# MCU.net
KiCad netlist of a schematic drawn in Altium Designer
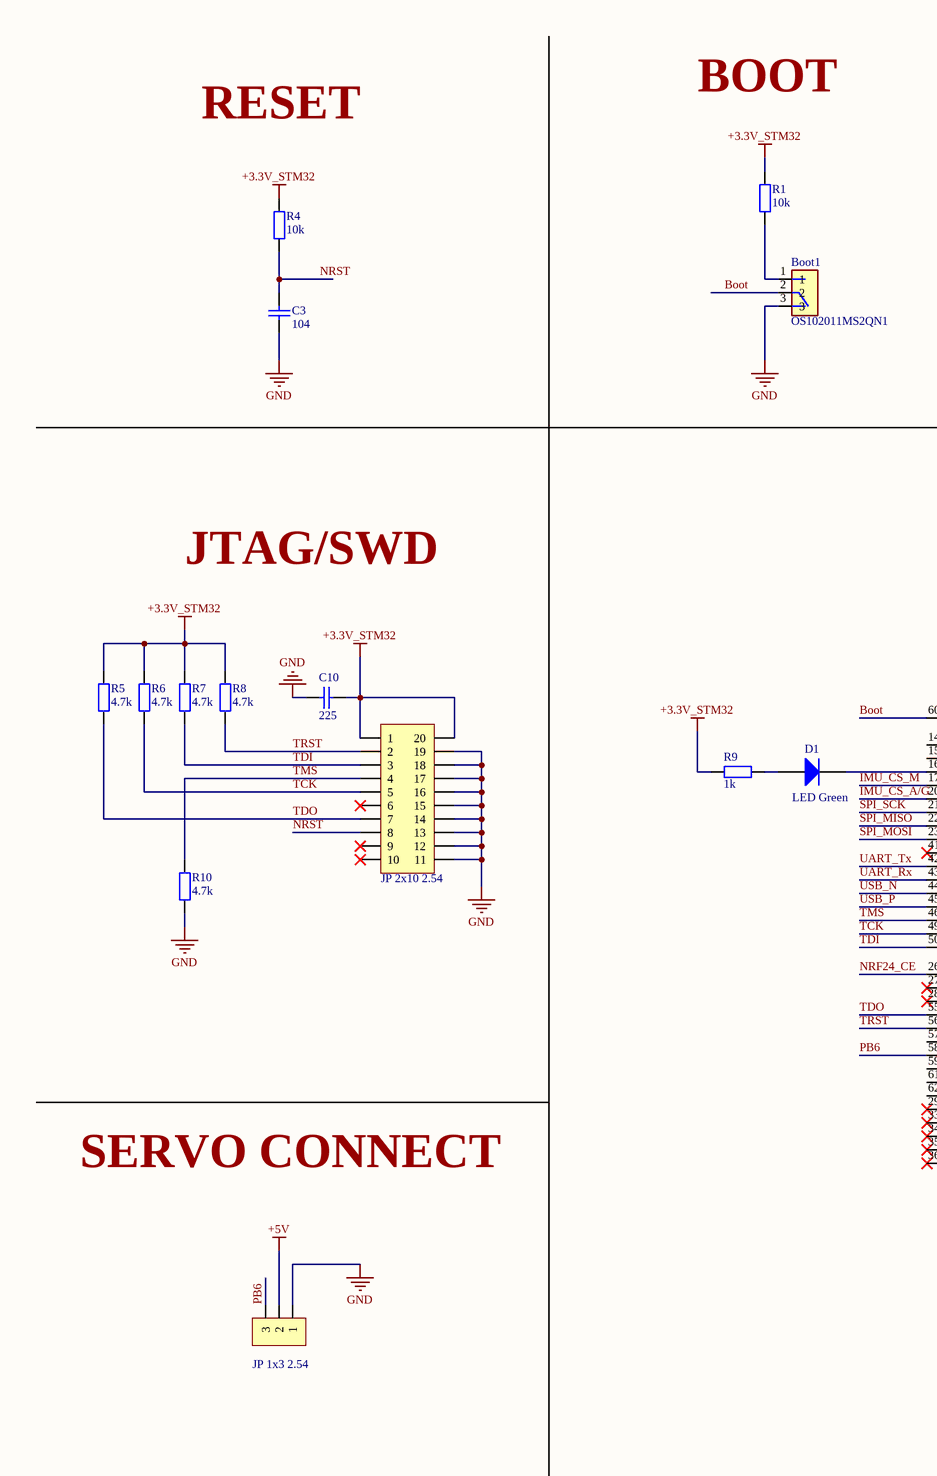
[diagram p0: MCU.SchDoc, left]
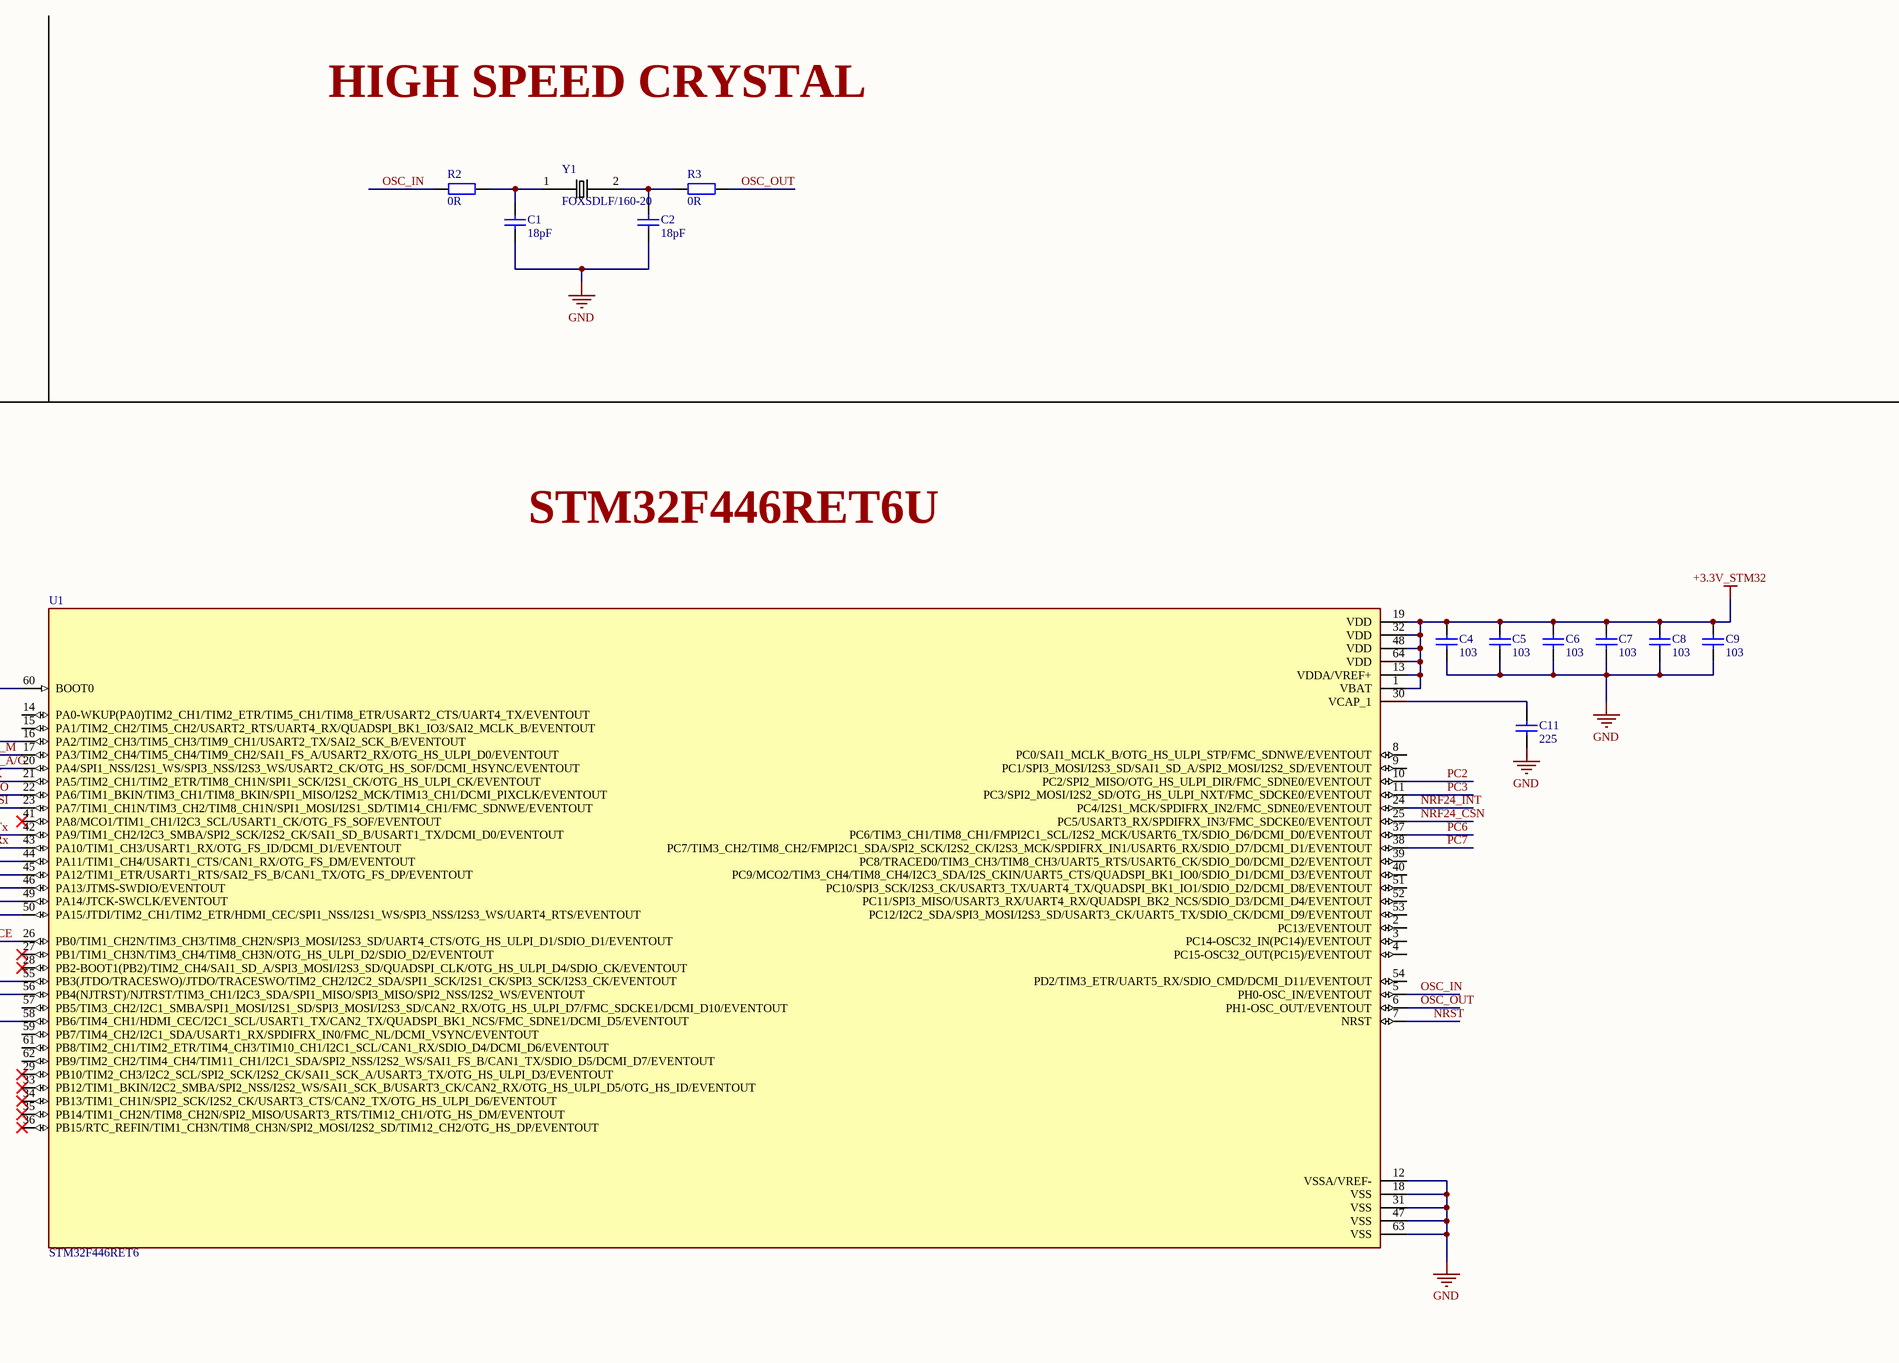
[diagram p1: MCU.SchDoc, right]

(export (version "E")
  (design (tool "Eeschema 10.0.6"))
  (components
    (comp (ref "Boot1")
      (value "OS102011MS2QN1")
      (footprint "OS102011MS2QN1:SW_OS102011MS2QN1")
      (description "Switch Slide ON ON SPDT Top Slide 0.1A 12VDC 10000Cycles PC Pins Thru-Hole Bulk")
      (fields (field (name "MF") "{'manufacturer': u'C&K'}"))
      (libsource (lib "*") (part "OS102011MS2QN1"))
    )
    (comp (ref "C1")
      (value "18pF")
      (footprint "tu 0805")
      (description "Dán")
      (libsource (lib "Altium_Lib_by_KhueNguyenCreator") (part "Tu 0805 20pF 50V 10%"))
    )
    (comp (ref "C2")
      (value "18pF")
      (footprint "tu 0805")
      (description "Dán")
      (libsource (lib "Altium_Lib_by_KhueNguyenCreator") (part "Tu 0805 20pF 50V 10%"))
    )
    (comp (ref "C3")
      (value "104")
      (footprint "tu 1206")
      (description "Dán")
      (libsource (lib "Altium_Lib_by_KhueNguyenCreator") (part "Tu 1206 104 50V 20%"))
    )
    (comp (ref "C4")
      (value "103")
      (footprint "tu 0603")
      (description "Dán")
      (libsource (lib "Altium_Lib_by_KhueNguyenCreator") (part "Tu 0603 103 50V 10%"))
    )
    (comp (ref "C5")
      (value "103")
      (footprint "tu 0603")
      (description "Dán")
      (libsource (lib "Altium_Lib_by_KhueNguyenCreator") (part "Tu 0603 103 50V 10%"))
    )
    (comp (ref "C6")
      (value "103")
      (footprint "tu 0603")
      (description "Dán")
      (libsource (lib "Altium_Lib_by_KhueNguyenCreator") (part "Tu 0603 103 50V 10%"))
    )
    (comp (ref "C7")
      (value "103")
      (footprint "tu 0603")
      (description "Dán")
      (libsource (lib "Altium_Lib_by_KhueNguyenCreator") (part "Tu 0603 103 50V 10%"))
    )
    (comp (ref "C8")
      (value "103")
      (footprint "tu 0603")
      (description "Dán")
      (libsource (lib "Altium_Lib_by_KhueNguyenCreator") (part "Tu 0603 103 50V 10%"))
    )
    (comp (ref "C9")
      (value "103")
      (footprint "tu 0603")
      (description "Dán")
      (libsource (lib "Altium_Lib_by_KhueNguyenCreator") (part "Tu 0603 103 50V 10%"))
    )
    (comp (ref "C10")
      (value "225")
      (footprint "tu 0805")
      (description "Dán")
      (libsource (lib "Altium_Lib_by_KhueNguyenCreator") (part "Tu 0805 225 25V 10%"))
    )
    (comp (ref "C11")
      (value "225")
      (footprint "tu 0805")
      (description "Dán")
      (libsource (lib "Altium_Lib_by_KhueNguyenCreator") (part "Tu 0805 225 25V 10%"))
    )
    (comp (ref "D1")
      (value "LED Green")
      (footprint "J1-0603")
      (description "Default Diode")
      (fields (field (name "PUBLISHER") "Altium Limited"))
      (libsource (lib "MSP430_sch_1060821") (part "Diode"))
    )
    (comp (ref "R1")
      (value "10k")
      (footprint "tro smd 0603")
      (description "Dán")
      (libsource (lib "Altium_Lib_by_KhueNguyenCreator") (part "Tro 0603 1% 10k"))
    )
    (comp (ref "R2")
      (value "0R")
      (footprint "tro smd 0603")
      (description "Dán")
      (libsource (lib "Altium_Lib_by_KhueNguyenCreator") (part "Tro 0603 1% 0R"))
    )
    (comp (ref "R3")
      (value "0R")
      (footprint "tro smd 0603")
      (description "Dán")
      (libsource (lib "Altium_Lib_by_KhueNguyenCreator") (part "Tro 0603 1% 0R"))
    )
    (comp (ref "R4")
      (value "10k")
      (footprint "tro smd 0603")
      (description "Dán")
      (libsource (lib "Altium_Lib_by_KhueNguyenCreator") (part "Tro 0603 1% 10k"))
    )
    (comp (ref "R5")
      (value "4.7k")
      (footprint "tro smd 0603")
      (description "Dán")
      (libsource (lib "Altium_Lib_by_KhueNguyenCreator") (part "Tro 0603 5% 4.7k"))
    )
    (comp (ref "R6")
      (value "4.7k")
      (footprint "tro smd 0603")
      (description "Dán")
      (libsource (lib "Altium_Lib_by_KhueNguyenCreator") (part "Tro 0603 5% 4.7k"))
    )
    (comp (ref "R7")
      (value "4.7k")
      (footprint "tro smd 0603")
      (description "Dán")
      (libsource (lib "Altium_Lib_by_KhueNguyenCreator") (part "Tro 0603 5% 4.7k"))
    )
    (comp (ref "R8")
      (value "4.7k")
      (footprint "tro smd 0603")
      (description "Dán")
      (libsource (lib "Altium_Lib_by_KhueNguyenCreator") (part "Tro 0603 5% 4.7k"))
    )
    (comp (ref "R9")
      (value "1k")
      (footprint "tro smd 0603")
      (description "Dán")
      (libsource (lib "Altium_Lib_by_KhueNguyenCreator") (part "Tro 0603 1% 1k"))
    )
    (comp (ref "R10")
      (value "4.7k")
      (footprint "tro smd 0603")
      (description "Dán")
      (libsource (lib "Altium_Lib_by_KhueNguyenCreator") (part "Tro 0603 5% 4.7k"))
    )
    (comp (ref "Servo1")
      (value "JP 1x3 2.54")
      (footprint "JP 1x3 DT")
      (description "Cắm")
      (libsource (lib "Altium_Lib_by_KhueNguyenCreator") (part "JP 1x3 2.54 Duc Thang"))
    )
    (comp (ref "SWD/JTAG1")
      (value "JP 2x10 2.54")
      (footprint "JP 2x10 DT")
      (description "Cắm")
      (libsource (lib "Altium_Lib_by_KhueNguyenCreator") (part "JP 2x10 2.54 Duc Thang"))
    )
    (comp (ref "U1")
      (value "STM32F446RET6")
      (footprint "STM32F446RET6:QFP50P1200X1200X160-64N")
      (description "MCU 32-Bit STM32 ARM Cortex M4 RISC 512KB Flash 2.5V/3.3V 64-Pin LQFP Tray")
      (fields (field (name "MF") "{'manufacturer': u'STMicroelectronics'}"))
      (libsource (lib "*") (part "STM32F446RET6"))
    )
    (comp (ref "Y1")
      (value "FOXSDLF/160-20")
      (footprint "SMD_Crystal")
      (description "Crystal 16MHz 20pF 2-Pin HC-49/SD")
      (fields (field (name "DIGI-KEY_PART_NUMBER") "631-1017-2-ND") (field (name "MF") "Fox"))
      (libsource (lib "MSP430_sch_1120816") (part "Crystal 16MHz 20pF 2-Pin"))
    )
  )
  (nets
    (net (code "1") (name "+3.3V_STM32") (class "Default")
      (node (ref "C10") (pin "1") (pinfunction "1_1") (pintype "passive"))
      (node (ref "C4") (pin "1") (pinfunction "1_1") (pintype "passive"))
      (node (ref "C5") (pin "1") (pinfunction "1_1") (pintype "passive"))
      (node (ref "C6") (pin "1") (pinfunction "1_1") (pintype "passive"))
      (node (ref "C7") (pin "1") (pinfunction "1_1") (pintype "passive"))
      (node (ref "C8") (pin "1") (pinfunction "1_1") (pintype "passive"))
      (node (ref "C9") (pin "1") (pinfunction "1_1") (pintype "passive"))
      (node (ref "R1") (pin "2") (pinfunction "2_2") (pintype "passive"))
      (node (ref "R4") (pin "2") (pinfunction "2_2") (pintype "passive"))
      (node (ref "R5") (pin "2") (pinfunction "2_2") (pintype "passive"))
      (node (ref "R6") (pin "2") (pinfunction "2_2") (pintype "passive"))
      (node (ref "R7") (pin "2") (pinfunction "2_2") (pintype "passive"))
      (node (ref "R8") (pin "2") (pinfunction "2_2") (pintype "passive"))
      (node (ref "R9") (pin "2") (pinfunction "2_2") (pintype "passive"))
      (node (ref "SWD/JTAG1") (pin "1") (pinfunction "1_1") (pintype "passive"))
      (node (ref "SWD/JTAG1") (pin "20") (pinfunction "20_20") (pintype "passive"))
      (node (ref "U1") (pin "1") (pinfunction "VBAT_1") (pintype "power_in"))
      (node (ref "U1") (pin "13") (pinfunction "VDDA/VREF+_13") (pintype "power_in"))
      (node (ref "U1") (pin "19") (pinfunction "VDD_19") (pintype "power_in"))
      (node (ref "U1") (pin "32") (pinfunction "VDD_32") (pintype "power_in"))
      (node (ref "U1") (pin "48") (pinfunction "VDD_48") (pintype "power_in"))
      (node (ref "U1") (pin "64") (pinfunction "VDD_64") (pintype "power_in"))
    )
    (net (code "2") (name "+5V") (class "Default")
      (node (ref "Servo1") (pin "2") (pinfunction "2_2") (pintype "passive"))
    )
    (net (code "3") (name "/Boot") (class "Default")
      (node (ref "Boot1") (pin "2") (pinfunction "2_2") (pintype "passive"))
      (node (ref "U1") (pin "60") (pinfunction "BOOT0_60") (pintype "input"))
    )
    (net (code "4") (name "/IMU_CS_A{slash}G") (class "Default")
      (node (ref "U1") (pin "20") (pinfunction "PA4/SPI1_NSS/I2S1_WS/SPI3_NSS/I2S3_WS/USART2_CK/OTG_HS_SOF/DCMI_HSYNC/EVENTOUT_20") (pintype "bidirectional"))
    )
    (net (code "5") (name "/IMU_CS_M") (class "Default")
      (node (ref "U1") (pin "17") (pinfunction "PA3/TIM2_CH4/TIM5_CH4/TIM9_CH2/SAI1_FS_A/USART2_RX/OTG_HS_ULPI_D0/EVENTOUT_17") (pintype "bidirectional"))
    )
    (net (code "6") (name "/NRF24_CE") (class "Default")
      (node (ref "U1") (pin "26") (pinfunction "PB0/TIM1_CH2N/TIM3_CH3/TIM8_CH2N/SPI3_MOSI/I2S3_SD/UART4_CTS/OTG_HS_ULPI_D1/SDIO_D1/EVENTOUT_26") (pintype "bidirectional"))
    )
    (net (code "7") (name "/NRF24_CSN") (class "Default")
      (node (ref "U1") (pin "25") (pinfunction "PC5/USART3_RX/SPDIFRX_IN3/FMC_SDCKE0/EVENTOUT_25") (pintype "bidirectional"))
    )
    (net (code "8") (name "/NRF24_INT") (class "Default")
      (node (ref "U1") (pin "24") (pinfunction "PC4/I2S1_MCK/SPDIFRX_IN2/FMC_SDNE0/EVENTOUT_24") (pintype "bidirectional"))
    )
    (net (code "9") (name "/NRST") (class "Default")
      (node (ref "C3") (pin "1") (pinfunction "1_1") (pintype "passive"))
      (node (ref "R4") (pin "1") (pinfunction "1_1") (pintype "passive"))
      (node (ref "SWD/JTAG1") (pin "8") (pinfunction "8_8") (pintype "passive"))
      (node (ref "U1") (pin "7") (pinfunction "NRST_7") (pintype "bidirectional"))
    )
    (net (code "10") (name "/OSC_IN") (class "Default")
      (node (ref "R2") (pin "1") (pinfunction "1_1") (pintype "passive"))
      (node (ref "U1") (pin "5") (pinfunction "PH0-OSC_IN/EVENTOUT_5") (pintype "bidirectional"))
    )
    (net (code "11") (name "/OSC_OUT") (class "Default")
      (node (ref "R3") (pin "2") (pinfunction "2_2") (pintype "passive"))
      (node (ref "U1") (pin "6") (pinfunction "PH1-OSC_OUT/EVENTOUT_6") (pintype "bidirectional"))
    )
    (net (code "12") (name "/PB6") (class "Default")
      (node (ref "Servo1") (pin "3") (pinfunction "3_3") (pintype "passive"))
      (node (ref "U1") (pin "58") (pinfunction "PB6/TIM4_CH1/HDMI_CEC/I2C1_SCL/USART1_TX/CAN2_TX/QUADSPI_BK1_NCS/FMC_SDNE1/DCMI_D5/EVENTOUT_58") (pintype "bidirectional"))
    )
    (net (code "13") (name "/PC2") (class "Default")
      (node (ref "U1") (pin "10") (pinfunction "PC2/SPI2_MISO/OTG_HS_ULPI_DIR/FMC_SDNE0/EVENTOUT_10") (pintype "bidirectional"))
    )
    (net (code "14") (name "/PC3") (class "Default")
      (node (ref "U1") (pin "11") (pinfunction "PC3/SPI2_MOSI/I2S2_SD/OTG_HS_ULPI_NXT/FMC_SDCKE0/EVENTOUT_11") (pintype "bidirectional"))
    )
    (net (code "15") (name "/PC6") (class "Default")
      (node (ref "U1") (pin "37") (pinfunction "PC6/TIM3_CH1/TIM8_CH1/FMPI2C1_SCL/I2S2_MCK/USART6_TX/SDIO_D6/DCMI_D0/EVENTOUT_37") (pintype "bidirectional"))
    )
    (net (code "16") (name "/PC7") (class "Default")
      (node (ref "U1") (pin "38") (pinfunction "PC7/TIM3_CH2/TIM8_CH2/FMPI2C1_SDA/SPI2_SCK/I2S2_CK/I2S3_MCK/SPDIFRX_IN1/USART6_RX/SDIO_D7/DCMI_D1/EVENTOUT_38") (pintype "bidirectional"))
    )
    (net (code "17") (name "/SPI_MISO") (class "Default")
      (node (ref "U1") (pin "22") (pinfunction "PA6/TIM1_BKIN/TIM3_CH1/TIM8_BKIN/SPI1_MISO/I2S2_MCK/TIM13_CH1/DCMI_PIXCLK/EVENTOUT_22") (pintype "bidirectional"))
    )
    (net (code "18") (name "/SPI_MOSI") (class "Default")
      (node (ref "U1") (pin "23") (pinfunction "PA7/TIM1_CH1N/TIM3_CH2/TIM8_CH1N/SPI1_MOSI/I2S1_SD/TIM14_CH1/FMC_SDNWE/EVENTOUT_23") (pintype "bidirectional"))
    )
    (net (code "19") (name "/SPI_SCK") (class "Default")
      (node (ref "U1") (pin "21") (pinfunction "PA5/TIM2_CH1/TIM2_ETR/TIM8_CH1N/SPI1_SCK/I2S1_CK/OTG_HS_ULPI_CK/EVENTOUT_21") (pintype "bidirectional"))
    )
    (net (code "20") (name "/TCK") (class "Default")
      (node (ref "R6") (pin "1") (pinfunction "1_1") (pintype "passive"))
      (node (ref "SWD/JTAG1") (pin "5") (pinfunction "5_5") (pintype "passive"))
      (node (ref "U1") (pin "49") (pinfunction "PA14/JTCK-SWCLK/EVENTOUT_49") (pintype "bidirectional"))
    )
    (net (code "21") (name "/TDI") (class "Default")
      (node (ref "R7") (pin "1") (pinfunction "1_1") (pintype "passive"))
      (node (ref "SWD/JTAG1") (pin "3") (pinfunction "3_3") (pintype "passive"))
      (node (ref "U1") (pin "50") (pinfunction "PA15/JTDI/TIM2_CH1/TIM2_ETR/HDMI_CEC/SPI1_NSS/I2S1_WS/SPI3_NSS/I2S3_WS/UART4_RTS/EVENTOUT_50") (pintype "bidirectional"))
    )
    (net (code "22") (name "/TDO") (class "Default")
      (node (ref "R5") (pin "1") (pinfunction "1_1") (pintype "passive"))
      (node (ref "SWD/JTAG1") (pin "7") (pinfunction "7_7") (pintype "passive"))
      (node (ref "U1") (pin "55") (pinfunction "PB3(JTDO/TRACESWO)/JTDO/TRACESWO/TIM2_CH2/I2C2_SDA/SPI1_SCK/I2S1_CK/SPI3_SCK/I2S3_CK/EVENTOUT_55") (pintype "bidirectional"))
    )
    (net (code "23") (name "/TMS") (class "Default")
      (node (ref "R10") (pin "2") (pinfunction "2_2") (pintype "passive"))
      (node (ref "SWD/JTAG1") (pin "4") (pinfunction "4_4") (pintype "passive"))
      (node (ref "U1") (pin "46") (pinfunction "PA13/JTMS-SWDIO/EVENTOUT_46") (pintype "bidirectional"))
    )
    (net (code "24") (name "/TRST") (class "Default")
      (node (ref "R8") (pin "1") (pinfunction "1_1") (pintype "passive"))
      (node (ref "SWD/JTAG1") (pin "2") (pinfunction "2_2") (pintype "passive"))
      (node (ref "U1") (pin "56") (pinfunction "PB4(NJTRST)/NJTRST/TIM3_CH1/I2C3_SDA/SPI1_MISO/SPI3_MISO/SPI2_NSS/I2S2_WS/EVENTOUT_56") (pintype "bidirectional"))
    )
    (net (code "25") (name "/UART_Rx") (class "Default")
      (node (ref "U1") (pin "43") (pinfunction "PA10/TIM1_CH3/USART1_RX/OTG_FS_ID/DCMI_D1/EVENTOUT_43") (pintype "bidirectional"))
    )
    (net (code "26") (name "/UART_Tx") (class "Default")
      (node (ref "U1") (pin "42") (pinfunction "PA9/TIM1_CH2/I2C3_SMBA/SPI2_SCK/I2S2_CK/SAI1_SD_B/USART1_TX/DCMI_D0/EVENTOUT_42") (pintype "bidirectional"))
    )
    (net (code "27") (name "/USB_N") (class "Default")
      (node (ref "U1") (pin "44") (pinfunction "PA11/TIM1_CH4/USART1_CTS/CAN1_RX/OTG_FS_DM/EVENTOUT_44") (pintype "bidirectional"))
    )
    (net (code "28") (name "/USB_P") (class "Default")
      (node (ref "U1") (pin "45") (pinfunction "PA12/TIM1_ETR/USART1_RTS/SAI2_FS_B/CAN1_TX/OTG_FS_DP/EVENTOUT_45") (pintype "bidirectional"))
    )
    (net (code "29") (name "GND") (class "Default")
      (node (ref "Boot1") (pin "3") (pinfunction "3_3") (pintype "passive"))
      (node (ref "C1") (pin "2") (pinfunction "2_2") (pintype "passive"))
      (node (ref "C10") (pin "2") (pinfunction "2_2") (pintype "passive"))
      (node (ref "C11") (pin "2") (pinfunction "2_2") (pintype "passive"))
      (node (ref "C2") (pin "2") (pinfunction "2_2") (pintype "passive"))
      (node (ref "C3") (pin "2") (pinfunction "2_2") (pintype "passive"))
      (node (ref "C4") (pin "2") (pinfunction "2_2") (pintype "passive"))
      (node (ref "C5") (pin "2") (pinfunction "2_2") (pintype "passive"))
      (node (ref "C6") (pin "2") (pinfunction "2_2") (pintype "passive"))
      (node (ref "C7") (pin "2") (pinfunction "2_2") (pintype "passive"))
      (node (ref "C8") (pin "2") (pinfunction "2_2") (pintype "passive"))
      (node (ref "C9") (pin "2") (pinfunction "2_2") (pintype "passive"))
      (node (ref "R10") (pin "1") (pinfunction "1_1") (pintype "passive"))
      (node (ref "SWD/JTAG1") (pin "11") (pinfunction "11_11") (pintype "passive"))
      (node (ref "SWD/JTAG1") (pin "12") (pinfunction "12_12") (pintype "passive"))
      (node (ref "SWD/JTAG1") (pin "13") (pinfunction "13_13") (pintype "passive"))
      (node (ref "SWD/JTAG1") (pin "14") (pinfunction "14_14") (pintype "passive"))
      (node (ref "SWD/JTAG1") (pin "15") (pinfunction "15_15") (pintype "passive"))
      (node (ref "SWD/JTAG1") (pin "16") (pinfunction "16_16") (pintype "passive"))
      (node (ref "SWD/JTAG1") (pin "17") (pinfunction "17_17") (pintype "passive"))
      (node (ref "SWD/JTAG1") (pin "18") (pinfunction "18_18") (pintype "passive"))
      (node (ref "SWD/JTAG1") (pin "19") (pinfunction "19_19") (pintype "passive"))
      (node (ref "Servo1") (pin "1") (pinfunction "1_1") (pintype "passive"))
      (node (ref "U1") (pin "12") (pinfunction "VSSA/VREF-_12") (pintype "power_in"))
      (node (ref "U1") (pin "18") (pinfunction "VSS_18") (pintype "power_in"))
      (node (ref "U1") (pin "31") (pinfunction "VSS_31") (pintype "power_in"))
      (node (ref "U1") (pin "47") (pinfunction "VSS_47") (pintype "power_in"))
      (node (ref "U1") (pin "63") (pinfunction "VSS_63") (pintype "power_in"))
    )
    (net (code "30") (name "Net-(Boot1-Pad1)") (class "Default")
      (node (ref "Boot1") (pin "1") (pinfunction "1_1") (pintype "passive"))
      (node (ref "R1") (pin "1") (pinfunction "1_1") (pintype "passive"))
    )
    (net (code "31") (name "Net-(C1-Pad1)") (class "Default")
      (node (ref "C1") (pin "1") (pinfunction "1_1") (pintype "passive"))
      (node (ref "R2") (pin "2") (pinfunction "2_2") (pintype "passive"))
      (node (ref "Y1") (pin "1") (pinfunction "1_1") (pintype "passive"))
    )
    (net (code "32") (name "Net-(C2-Pad1)") (class "Default")
      (node (ref "C2") (pin "1") (pinfunction "1_1") (pintype "passive"))
      (node (ref "R3") (pin "1") (pinfunction "1_1") (pintype "passive"))
      (node (ref "Y1") (pin "2") (pinfunction "2_2") (pintype "passive"))
    )
    (net (code "33") (name "Net-(D1-A)") (class "Default")
      (node (ref "D1") (pin "1") (pinfunction "A_1") (pintype "passive"))
      (node (ref "R9") (pin "1") (pinfunction "1_1") (pintype "passive"))
    )
    (net (code "34") (name "Net-(D1-K)") (class "Default")
      (node (ref "D1") (pin "2") (pinfunction "K_2") (pintype "passive"))
      (node (ref "U1") (pin "16") (pinfunction "PA2/TIM2_CH3/TIM5_CH3/TIM9_CH1/USART2_TX/SAI2_SCK_B/EVENTOUT_16") (pintype "bidirectional"))
    )
    (net (code "35") (name "Net-(U1-VCAP_1)") (class "Default")
      (node (ref "C11") (pin "1") (pinfunction "1_1") (pintype "passive"))
      (node (ref "U1") (pin "30") (pinfunction "VCAP_1_30") (pintype "power_in"))
    )
    (net (code "36") (name "unconnected-(SWD/JTAG1-Pad6)") (class "Default")
      (node (ref "SWD/JTAG1") (pin "6") (pinfunction "6_6") (pintype "passive+no_connect"))
    )
    (net (code "37") (name "unconnected-(SWD/JTAG1-Pad9)") (class "Default")
      (node (ref "SWD/JTAG1") (pin "9") (pinfunction "9_9") (pintype "passive+no_connect"))
    )
    (net (code "38") (name "unconnected-(SWD/JTAG1-Pad10)") (class "Default")
      (node (ref "SWD/JTAG1") (pin "10") (pinfunction "10_10") (pintype "passive+no_connect"))
    )
    (net (code "39") (name "unconnected-(U1-PA0-WKUP(PA0)TIM2_CH1{slash}TIM2_ETR{slash}TIM5_CH1{slash}TIM8_ETR{slash}USART2_CTS{slash}UART4_TX{slash}EVENTOUT-Pad14)") (class "Default")
      (node (ref "U1") (pin "14") (pinfunction "PA0-WKUP(PA0)TIM2_CH1/TIM2_ETR/TIM5_CH1/TIM8_ETR/USART2_CTS/UART4_TX/EVENTOUT_14") (pintype "bidirectional"))
    )
    (net (code "40") (name "unconnected-(U1-PA1{slash}TIM2_CH2{slash}TIM5_CH2{slash}USART2_RTS{slash}UART4_RX{slash}QUADSPI_BK1_IO3{slash}SAI2_MCLK_B{slash}EVENTOUT-Pad15)") (class "Default")
      (node (ref "U1") (pin "15") (pinfunction "PA1/TIM2_CH2/TIM5_CH2/USART2_RTS/UART4_RX/QUADSPI_BK1_IO3/SAI2_MCLK_B/EVENTOUT_15") (pintype "bidirectional"))
    )
    (net (code "41") (name "unconnected-(U1-PA8{slash}MCO1{slash}TIM1_CH1{slash}I2C3_SCL{slash}USART1_CK{slash}OTG_FS_SOF{slash}EVENTOUT-Pad41)") (class "Default")
      (node (ref "U1") (pin "41") (pinfunction "PA8/MCO1/TIM1_CH1/I2C3_SCL/USART1_CK/OTG_FS_SOF/EVENTOUT_41") (pintype "bidirectional+no_connect"))
    )
    (net (code "42") (name "unconnected-(U1-PB1{slash}TIM1_CH3N{slash}TIM3_CH4{slash}TIM8_CH3N{slash}OTG_HS_ULPI_D2{slash}SDIO_D2{slash}EVENTOUT-Pad27)") (class "Default")
      (node (ref "U1") (pin "27") (pinfunction "PB1/TIM1_CH3N/TIM3_CH4/TIM8_CH3N/OTG_HS_ULPI_D2/SDIO_D2/EVENTOUT_27") (pintype "bidirectional+no_connect"))
    )
    (net (code "43") (name "unconnected-(U1-PB2-BOOT1(PB2){slash}TIM2_CH4{slash}SAI1_SD_A{slash}SPI3_MOSI{slash}I2S3_SD{slash}QUADSPI_CLK{slash}OTG_HS_ULPI_D4{slash}SDIO_CK{slash}EVENTOUT-Pad28)") (class "Default")
      (node (ref "U1") (pin "28") (pinfunction "PB2-BOOT1(PB2)/TIM2_CH4/SAI1_SD_A/SPI3_MOSI/I2S3_SD/QUADSPI_CLK/OTG_HS_ULPI_D4/SDIO_CK/EVENTOUT_28") (pintype "bidirectional+no_connect"))
    )
    (net (code "44") (name "unconnected-(U1-PB5{slash}TIM3_CH2{slash}I2C1_SMBA{slash}SPI1_MOSI{slash}I2S1_SD{slash}SPI3_MOSI{slash}I2S3_SD{slash}CAN2_RX{slash}OTG_HS_ULPI_D7{slash}FMC_SDCKE1{slash}DCMI_D10{slash}EVENTOUT-Pad57)") (class "Default")
      (node (ref "U1") (pin "57") (pinfunction "PB5/TIM3_CH2/I2C1_SMBA/SPI1_MOSI/I2S1_SD/SPI3_MOSI/I2S3_SD/CAN2_RX/OTG_HS_ULPI_D7/FMC_SDCKE1/DCMI_D10/EVENTOUT_57") (pintype "bidirectional"))
    )
    (net (code "45") (name "unconnected-(U1-PB7{slash}TIM4_CH2{slash}I2C1_SDA{slash}USART1_RX{slash}SPDIFRX_IN0{slash}FMC_NL{slash}DCMI_VSYNC{slash}EVENTOUT-Pad59)") (class "Default")
      (node (ref "U1") (pin "59") (pinfunction "PB7/TIM4_CH2/I2C1_SDA/USART1_RX/SPDIFRX_IN0/FMC_NL/DCMI_VSYNC/EVENTOUT_59") (pintype "bidirectional"))
    )
    (net (code "46") (name "unconnected-(U1-PB8{slash}TIM2_CH1{slash}TIM2_ETR{slash}TIM4_CH3{slash}TIM10_CH1{slash}I2C1_SCL{slash}CAN1_RX{slash}SDIO_D4{slash}DCMI_D6{slash}EVENTOUT-Pad61)") (class "Default")
      (node (ref "U1") (pin "61") (pinfunction "PB8/TIM2_CH1/TIM2_ETR/TIM4_CH3/TIM10_CH1/I2C1_SCL/CAN1_RX/SDIO_D4/DCMI_D6/EVENTOUT_61") (pintype "bidirectional"))
    )
    (net (code "47") (name "unconnected-(U1-PB9{slash}TIM2_CH2{slash}TIM4_CH4{slash}TIM11_CH1{slash}I2C1_SDA{slash}SPI2_NSS{slash}I2S2_WS{slash}SAI1_FS_B{slash}CAN1_TX{slash}SDIO_D5{slash}DCMI_D7{slash}EVENTOUT-Pad62)") (class "Default")
      (node (ref "U1") (pin "62") (pinfunction "PB9/TIM2_CH2/TIM4_CH4/TIM11_CH1/I2C1_SDA/SPI2_NSS/I2S2_WS/SAI1_FS_B/CAN1_TX/SDIO_D5/DCMI_D7/EVENTOUT_62") (pintype "bidirectional"))
    )
    (net (code "48") (name "unconnected-(U1-PB10{slash}TIM2_CH3{slash}I2C2_SCL{slash}SPI2_SCK{slash}I2S2_CK{slash}SAI1_SCK_A{slash}USART3_TX{slash}OTG_HS_ULPI_D3{slash}EVENTOUT-Pad29)") (class "Default")
      (node (ref "U1") (pin "29") (pinfunction "PB10/TIM2_CH3/I2C2_SCL/SPI2_SCK/I2S2_CK/SAI1_SCK_A/USART3_TX/OTG_HS_ULPI_D3/EVENTOUT_29") (pintype "bidirectional+no_connect"))
    )
    (net (code "49") (name "unconnected-(U1-PB12{slash}TIM1_BKIN{slash}I2C2_SMBA{slash}SPI2_NSS{slash}I2S2_WS{slash}SAI1_SCK_B{slash}USART3_CK{slash}CAN2_RX{slash}OTG_HS_ULPI_D5{slash}OTG_HS_ID{slash}EVENTOUT-Pad33)") (class "Default")
      (node (ref "U1") (pin "33") (pinfunction "PB12/TIM1_BKIN/I2C2_SMBA/SPI2_NSS/I2S2_WS/SAI1_SCK_B/USART3_CK/CAN2_RX/OTG_HS_ULPI_D5/OTG_HS_ID/EVENTOUT_33") (pintype "bidirectional+no_connect"))
    )
    (net (code "50") (name "unconnected-(U1-PB13{slash}TIM1_CH1N{slash}SPI2_SCK{slash}I2S2_CK{slash}USART3_CTS{slash}CAN2_TX{slash}OTG_HS_ULPI_D6{slash}EVENTOUT-Pad34)") (class "Default")
      (node (ref "U1") (pin "34") (pinfunction "PB13/TIM1_CH1N/SPI2_SCK/I2S2_CK/USART3_CTS/CAN2_TX/OTG_HS_ULPI_D6/EVENTOUT_34") (pintype "bidirectional+no_connect"))
    )
    (net (code "51") (name "unconnected-(U1-PB14{slash}TIM1_CH2N{slash}TIM8_CH2N{slash}SPI2_MISO{slash}USART3_RTS{slash}TIM12_CH1{slash}OTG_HS_DM{slash}EVENTOUT-Pad35)") (class "Default")
      (node (ref "U1") (pin "35") (pinfunction "PB14/TIM1_CH2N/TIM8_CH2N/SPI2_MISO/USART3_RTS/TIM12_CH1/OTG_HS_DM/EVENTOUT_35") (pintype "bidirectional+no_connect"))
    )
    (net (code "52") (name "unconnected-(U1-PB15{slash}RTC_REFIN{slash}TIM1_CH3N{slash}TIM8_CH3N{slash}SPI2_MOSI{slash}I2S2_SD{slash}TIM12_CH2{slash}OTG_HS_DP{slash}EVENTOUT-Pad36)") (class "Default")
      (node (ref "U1") (pin "36") (pinfunction "PB15/RTC_REFIN/TIM1_CH3N/TIM8_CH3N/SPI2_MOSI/I2S2_SD/TIM12_CH2/OTG_HS_DP/EVENTOUT_36") (pintype "bidirectional+no_connect"))
    )
    (net (code "53") (name "unconnected-(U1-PC0{slash}SAI1_MCLK_B{slash}OTG_HS_ULPI_STP{slash}FMC_SDNWE{slash}EVENTOUT-Pad8)") (class "Default")
      (node (ref "U1") (pin "8") (pinfunction "PC0/SAI1_MCLK_B/OTG_HS_ULPI_STP/FMC_SDNWE/EVENTOUT_8") (pintype "bidirectional"))
    )
    (net (code "54") (name "unconnected-(U1-PC1{slash}SPI3_MOSI{slash}I2S3_SD{slash}SAI1_SD_A{slash}SPI2_MOSI{slash}I2S2_SD{slash}EVENTOUT-Pad9)") (class "Default")
      (node (ref "U1") (pin "9") (pinfunction "PC1/SPI3_MOSI/I2S3_SD/SAI1_SD_A/SPI2_MOSI/I2S2_SD/EVENTOUT_9") (pintype "bidirectional"))
    )
    (net (code "55") (name "unconnected-(U1-PC8{slash}TRACED0{slash}TIM3_CH3{slash}TIM8_CH3{slash}UART5_RTS{slash}USART6_CK{slash}SDIO_D0{slash}DCMI_D2{slash}EVENTOUT-Pad39)") (class "Default")
      (node (ref "U1") (pin "39") (pinfunction "PC8/TRACED0/TIM3_CH3/TIM8_CH3/UART5_RTS/USART6_CK/SDIO_D0/DCMI_D2/EVENTOUT_39") (pintype "bidirectional"))
    )
    (net (code "56") (name "unconnected-(U1-PC9{slash}MCO2{slash}TIM3_CH4{slash}TIM8_CH4{slash}I2C3_SDA{slash}I2S_CKIN{slash}UART5_CTS{slash}QUADSPI_BK1_IO0{slash}SDIO_D1{slash}DCMI_D3{slash}EVENTOUT-Pad40)") (class "Default")
      (node (ref "U1") (pin "40") (pinfunction "PC9/MCO2/TIM3_CH4/TIM8_CH4/I2C3_SDA/I2S_CKIN/UART5_CTS/QUADSPI_BK1_IO0/SDIO_D1/DCMI_D3/EVENTOUT_40") (pintype "bidirectional"))
    )
    (net (code "57") (name "unconnected-(U1-PC10{slash}SPI3_SCK{slash}I2S3_CK{slash}USART3_TX{slash}UART4_TX{slash}QUADSPI_BK1_IO1{slash}SDIO_D2{slash}DCMI_D8{slash}EVENTOUT-Pad51)") (class "Default")
      (node (ref "U1") (pin "51") (pinfunction "PC10/SPI3_SCK/I2S3_CK/USART3_TX/UART4_TX/QUADSPI_BK1_IO1/SDIO_D2/DCMI_D8/EVENTOUT_51") (pintype "bidirectional"))
    )
    (net (code "58") (name "unconnected-(U1-PC11{slash}SPI3_MISO{slash}USART3_RX{slash}UART4_RX{slash}QUADSPI_BK2_NCS{slash}SDIO_D3{slash}DCMI_D4{slash}EVENTOUT-Pad52)") (class "Default")
      (node (ref "U1") (pin "52") (pinfunction "PC11/SPI3_MISO/USART3_RX/UART4_RX/QUADSPI_BK2_NCS/SDIO_D3/DCMI_D4/EVENTOUT_52") (pintype "bidirectional"))
    )
    (net (code "59") (name "unconnected-(U1-PC12{slash}I2C2_SDA{slash}SPI3_MOSI{slash}I2S3_SD{slash}USART3_CK{slash}UART5_TX{slash}SDIO_CK{slash}DCMI_D9{slash}EVENTOUT-Pad53)") (class "Default")
      (node (ref "U1") (pin "53") (pinfunction "PC12/I2C2_SDA/SPI3_MOSI/I2S3_SD/USART3_CK/UART5_TX/SDIO_CK/DCMI_D9/EVENTOUT_53") (pintype "bidirectional"))
    )
    (net (code "60") (name "unconnected-(U1-PC13{slash}EVENTOUT-Pad2)") (class "Default")
      (node (ref "U1") (pin "2") (pinfunction "PC13/EVENTOUT_2") (pintype "bidirectional"))
    )
    (net (code "61") (name "unconnected-(U1-PC14-OSC32_IN(PC14){slash}EVENTOUT-Pad3)") (class "Default")
      (node (ref "U1") (pin "3") (pinfunction "PC14-OSC32_IN(PC14)/EVENTOUT_3") (pintype "bidirectional"))
    )
    (net (code "62") (name "unconnected-(U1-PC15-OSC32_OUT(PC15){slash}EVENTOUT-Pad4)") (class "Default")
      (node (ref "U1") (pin "4") (pinfunction "PC15-OSC32_OUT(PC15)/EVENTOUT_4") (pintype "bidirectional"))
    )
    (net (code "63") (name "unconnected-(U1-PD2{slash}TIM3_ETR{slash}UART5_RX{slash}SDIO_CMD{slash}DCMI_D11{slash}EVENTOUT-Pad54)") (class "Default")
      (node (ref "U1") (pin "54") (pinfunction "PD2/TIM3_ETR/UART5_RX/SDIO_CMD/DCMI_D11/EVENTOUT_54") (pintype "bidirectional"))
    )
  )
)
